# main.net
KiCad netlist of a schematic drawn in EAGLE
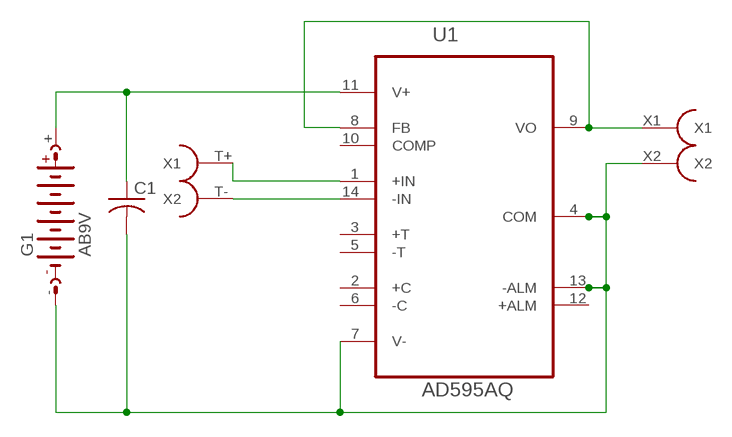
[diagram p0: schematic, sheet 1]

(export (version "E")
  (design (tool "Eeschema 10.0.6"))
  (components
    (comp (ref "C1")
      (value "C-USC0603")
      (footprint "eagle-import:C0603")
      (libsource (lib "eagle-import") (part "C-USC0603"))
    )
    (comp (ref "G1")
      (value "AB9V")
      (footprint "eagle-import:AB9V")
      (libsource (lib "eagle-import") (part "AB9V"))
    )
    (comp (ref "IN")
      (value "THERMOCOUPLE")
      (footprint "eagle-import:THERMOCOUPLE")
      (libsource (lib "eagle-import") (part "THERMOCOUPLE"))
    )
    (comp (ref "OUT")
      (value "BANANA_19MM")
      (footprint "eagle-import:BANANA_19MM")
      (libsource (lib "eagle-import") (part "BANANA_19MM"))
    )
    (comp (ref "U1")
      (value "AD595AQ")
      (footprint "eagle-import:DIP254P762X528-14P")
      (libsource (lib "eagle-import") (part "AD595AQ"))
    )
  )
  (nets
    (net (code "1") (name "Net-(IN-X1)") (class "Default")
      (node (ref "IN") (pin "T+") (pinfunction "X1_T+") (pintype "bidirectional"))
      (node (ref "U1") (pin "1") (pinfunction "+IN_1") (pintype "passive"))
    )
    (net (code "2") (name "Net-(IN-X2)") (class "Default")
      (node (ref "IN") (pin "T-") (pinfunction "X2_T-") (pintype "bidirectional"))
      (node (ref "U1") (pin "14") (pinfunction "-IN_14") (pintype "passive"))
    )
    (net (code "3") (name "Net-(U1--ALM)") (class "Default")
      (node (ref "C1") (pin "2") (pinfunction "2_2") (pintype "passive"))
      (node (ref "G1") (pin "-") (pinfunction "-_-") (pintype "passive"))
      (node (ref "OUT") (pin "X2") (pinfunction "X2_X2") (pintype "bidirectional"))
      (node (ref "U1") (pin "13") (pinfunction "-ALM_13") (pintype "passive"))
      (node (ref "U1") (pin "4") (pinfunction "COM_4") (pintype "passive"))
      (node (ref "U1") (pin "7") (pinfunction "V-_7") (pintype "power_in"))
    )
    (net (code "4") (name "Net-(U1-FB)") (class "Default")
      (node (ref "OUT") (pin "X1") (pinfunction "X1_X1") (pintype "bidirectional"))
      (node (ref "U1") (pin "8") (pinfunction "FB_8") (pintype "passive"))
      (node (ref "U1") (pin "9") (pinfunction "VO_9") (pintype "passive"))
    )
    (net (code "5") (name "Net-(U1-V+)") (class "Default")
      (node (ref "C1") (pin "1") (pinfunction "1_1") (pintype "passive"))
      (node (ref "G1") (pin "+") (pinfunction "+_+") (pintype "passive"))
      (node (ref "U1") (pin "11") (pinfunction "V+_11") (pintype "power_in"))
    )
    (net (code "6") (name "unconnected-(U1-+ALM-Pad12)") (class "Default")
      (node (ref "U1") (pin "12") (pinfunction "+ALM_12") (pintype "passive"))
    )
    (net (code "7") (name "unconnected-(U1-+C-Pad2)") (class "Default")
      (node (ref "U1") (pin "2") (pinfunction "+C_2") (pintype "passive"))
    )
    (net (code "8") (name "unconnected-(U1-+T-Pad3)") (class "Default")
      (node (ref "U1") (pin "3") (pinfunction "+T_3") (pintype "passive"))
    )
    (net (code "9") (name "unconnected-(U1--C-Pad6)") (class "Default")
      (node (ref "U1") (pin "6") (pinfunction "-C_6") (pintype "passive"))
    )
    (net (code "10") (name "unconnected-(U1--T-Pad5)") (class "Default")
      (node (ref "U1") (pin "5") (pinfunction "-T_5") (pintype "passive"))
    )
    (net (code "11") (name "unconnected-(U1-COMP-Pad10)") (class "Default")
      (node (ref "U1") (pin "10") (pinfunction "COMP_10") (pintype "passive"))
    )
  )
)
